# SiPM_ASSY_3mm.net
KiCad netlist of a schematic drawn in Altium Designer
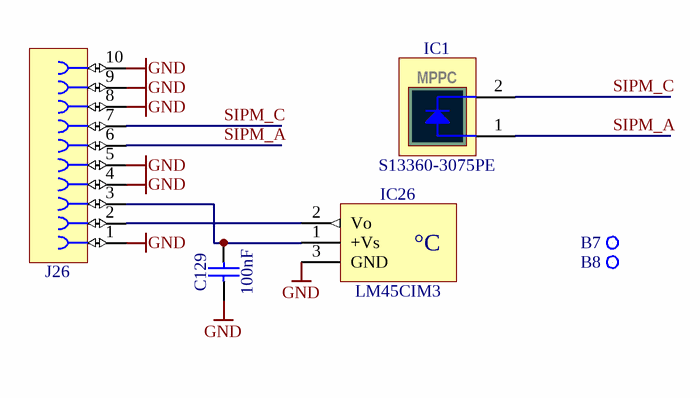
[diagram p0: SiPM_ASSY_3mm.SchDoc]

(export (version "E")
  (design (tool "Eeschema 10.0.6"))
  (components
    (comp (ref "B7")
      (value "Plated Hole")
      (footprint "MTG270_500")
      (description "Single Terminal Socket")
      (fields (field (name "PART NUMBER") "PLATED_HOLE2.7_PAD5.0") (field (name "AUTHOR") "CERN DEM JMW"))
      (libsource (lib "Eletro-mechanical") (part "Single Terminal Socket"))
    )
    (comp (ref "B8")
      (value "Plated Hole")
      (footprint "MTG270_500")
      (description "Single Terminal Socket")
      (fields (field (name "PART NUMBER") "PLATED_HOLE2.7_PAD5.0") (field (name "AUTHOR") "CERN DEM JMW"))
      (libsource (lib "Eletro-mechanical") (part "Single Terminal Socket"))
    )
    (comp (ref "C129")
      (value "100nF")
      (footprint "CAPC1005X55N")
      (description "Non-polarised capacitor")
      (fields
        (field (name "PART NUMBER") "CC0402_100NF_16V_10%_X7R")
        (field (name "VOLTAGE") "16V")
        (field (name "AUTHOR") "CERN DEM JLC")
      )
      (libsource (lib "Capacitors") (part "Capacitor - non polarized"))
    )
    (comp (ref "IC1")
      (value "S13360-3075PE")
      (footprint "HAMAMATSU_S13360-3075PE")
      (description "MPPC (Multi-Pixel Photon Counter)")
      (fields (field (name "MANUFACTURER") "HAMAMATSU") (field (name "AUTHOR") "GK"))
      (libsource (lib "Sensors") (part "SENS_S13360-3075PE"))
    )
    (comp (ref "IC26")
      (value "LM45CIM3")
      (footprint "SOT95P251X112-3N")
      (description "-20° to +100°C ±3°C Precision Centigrade Temperature Sensors")
      (fields (field (name "MANUFACTURER") "NATIONAL SEMICONDUCTOR") (field (name "AUTHOR") "CERN DEM JLC"))
      (libsource (lib "ICs And Semiconductors") (part "LM45"))
    )
    (comp (ref "J26")
      (value "FFC/FPC")
      (footprint "MOLEX_52745-1097")
      (description "Connector 10 Female")
      (fields
        (field (name "PART NUMBER") "MOLEX_52745-1097")
        (field (name "MANUFACTURER") "MOLEX")
        (field (name "AUTHOR") "CERN DEM JLC")
      )
      (libsource (lib "Connectors") (part "Connector 10 Female"))
    )
  )
  (nets
    (net (code "1") (name "/SIPM_A") (class "Default")
      (node (ref "IC1") (pin "1") (pinfunction "A_1") (pintype "passive"))
      (node (ref "J26") (pin "6") (pinfunction "6_6") (pintype "bidirectional"))
    )
    (net (code "2") (name "/SIPM_C") (class "Default")
      (node (ref "IC1") (pin "2") (pinfunction "C_2") (pintype "passive"))
      (node (ref "J26") (pin "7") (pinfunction "7_7") (pintype "bidirectional"))
    )
    (net (code "3") (name "GND") (class "Default")
      (node (ref "C129") (pin "1") (pinfunction "1_1") (pintype "passive"))
      (node (ref "IC26") (pin "3") (pinfunction "GND_3") (pintype "power_in"))
      (node (ref "J26") (pin "1") (pinfunction "1_1") (pintype "bidirectional"))
      (node (ref "J26") (pin "10") (pinfunction "10_10") (pintype "bidirectional"))
      (node (ref "J26") (pin "4") (pinfunction "4_4") (pintype "bidirectional"))
      (node (ref "J26") (pin "5") (pinfunction "5_5") (pintype "bidirectional"))
      (node (ref "J26") (pin "8") (pinfunction "8_8") (pintype "bidirectional"))
      (node (ref "J26") (pin "9") (pinfunction "9_9") (pintype "bidirectional"))
    )
    (net (code "4") (name "Net-(IC26-+Vs)") (class "Default")
      (node (ref "C129") (pin "2") (pinfunction "2_2") (pintype "passive"))
      (node (ref "IC26") (pin "1") (pinfunction "+Vs_1") (pintype "power_in"))
      (node (ref "J26") (pin "3") (pinfunction "3_3") (pintype "bidirectional"))
    )
    (net (code "5") (name "Net-(IC26-Vo)") (class "Default")
      (node (ref "IC26") (pin "2") (pinfunction "Vo_2") (pintype "output"))
      (node (ref "J26") (pin "2") (pinfunction "2_2") (pintype "bidirectional"))
    )
    (net (code "6") (name "unconnected-(B7-Pad1)") (class "Default")
      (node (ref "B7") (pin "1") (pinfunction "1_1") (pintype "bidirectional"))
    )
    (net (code "7") (name "unconnected-(B8-Pad1)") (class "Default")
      (node (ref "B8") (pin "1") (pinfunction "1_1") (pintype "bidirectional"))
    )
  )
)
